# PFC-120W.net
KiCad netlist of a schematic drawn in Altium Designer
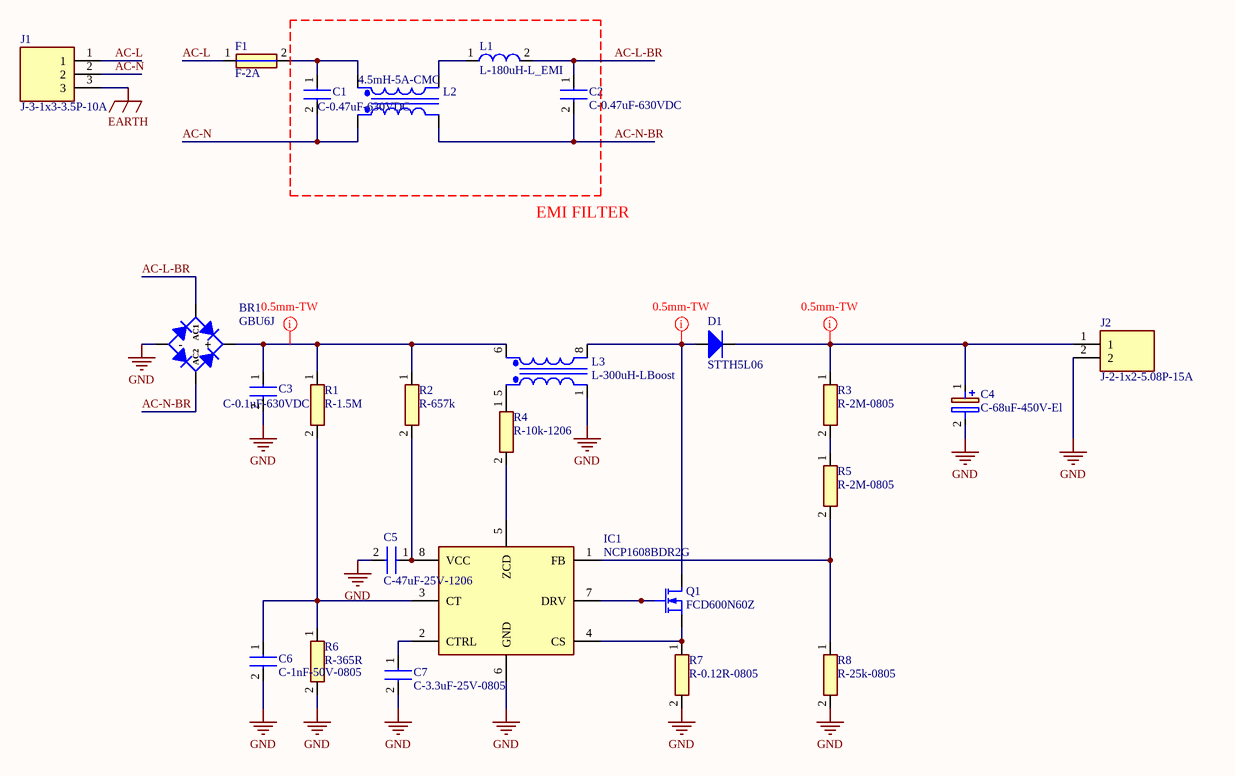
[diagram p0: PFC-120W.SchDoc]

(export (version "E")
  (design (tool "Eeschema 10.0.6"))
  (components
    (comp (ref "BR1")
      (value "GBU6J")
      (footprint "PFC-120W-Pcb-Lib:GBU6J")
      (description "Bridge Rectifier")
      (fields (field (name "MOUSER PART NUMBER") "905-GBU6J"))
      (libsource (lib "PFC-120W-Sch-Lib") (part "GBU6J"))
    )
    (comp (ref "C1")
      (value "C-0.47uF-630VDC")
      (footprint "PFC-120W-Pcb-Lib:ECWFA2J474JC")
      (description "Capacitor")
      (fields (field (name "MANUFACTURER_PART_NUMBER") "ECW-FA2J474JC"))
      (libsource (lib "PFC-120W-Sch-Lib") (part "C-0.47uF-630VDC"))
    )
    (comp (ref "C2")
      (value "C-0.47uF-630VDC")
      (footprint "PFC-120W-Pcb-Lib:ECWFA2J474JC")
      (description "Capacitor")
      (fields (field (name "MANUFACTURER_PART_NUMBER") "ECW-FA2J474JC"))
      (libsource (lib "PFC-120W-Sch-Lib") (part "C-0.47uF-630VDC"))
    )
    (comp (ref "C3")
      (value "C-0.1uF-630VDC")
      (footprint "PFC-120W-Pcb-Lib:BFC233923104")
      (description "Capacitor")
      (fields
        (field (name "MANUFACTURER_PART_NUMBER") "BFC233923104")
        (field (name "MOUSER PART NUMBER") "594-2222-339-23104")
      )
      (libsource (lib "PFC-120W-Sch-Lib") (part "C-0.1uF-630VDC"))
    )
    (comp (ref "C4")
      (value "C-68uF-450V-El")
      (footprint "PFC-120W-Pcb-Lib:CAPPRD750W80D1825H3750")
      (description "Capacitor Polarised")
      (fields (field (name "MANUFACTURER_PART_NUMBER") "UVY2W680MHD"))
      (libsource (lib "PFC-120W-Sch-Lib") (part "C-68uF-450V-El"))
    )
    (comp (ref "C5")
      (value "C-47uF-25V-1206")
      (footprint "PFC-120W-Pcb-Lib:CAPC3216X180N")
      (description "Capacitor")
      (fields
        (field (name "MANUFACTURER_PART_NUMBER") "C3216X5R1E476M160AC")
        (field (name "MOUSER PART NUMBER") "810-C3216X5R1E476M")
      )
      (libsource (lib "PFC-120W-Sch-Lib") (part "C-47uF-25V-1206"))
    )
    (comp (ref "C6")
      (value "C-1nF-50V-0805")
      (footprint "PFC-120W-Pcb-Lib:CAPC2012X135N")
      (description "Capacitor")
      (fields
        (field (name "MANUFACTURER_PART_NUMBER") "885382207004")
        (field (name "MOUSER PART NUMBER") "710-885382207004")
      )
      (libsource (lib "PFC-120W-Sch-Lib") (part "C-1nF-50V-0805"))
    )
    (comp (ref "C7")
      (value "C-3.3uF-25V-0805")
      (footprint "PFC-120W-Pcb-Lib:CAPC2012X145N")
      (description "Capacitor")
      (fields
        (field (name "MANUFACTURER_PART_NUMBER") "C2012X7R1E335M125AB")
        (field (name "MOUSER PART NUMBER") "810-C2012X7R1E335M")
      )
      (libsource (lib "PFC-120W-Sch-Lib") (part "C-3.3uF-25V-0805"))
    )
    (comp (ref "D1")
      (value "STTH5L06")
      (footprint "DPAK-STTH5L06")
      (description "Diode")
      (fields
        (field (name "MANUFACTURER") "STMicroelectronics")
        (field (name "MANUFACTURER PART NUMBER") "STTH5L06FP")
      )
      (libsource (lib "PFC-120W-Sch-Lib") (part "STTH5L06"))
    )
    (comp (ref "F1")
      (value "F-2A")
      (footprint "PFC-120W-Pcb-Lib:FUSC10131X312N")
      (description "Fuse")
      (fields
        (field (name "MANUFACTURER_PART_NUMBER") "0461002.ERT")
        (field (name "MOUSER PART NUMBER") "576-0461002.ERT")
      )
      (libsource (lib "PFC-120W-Sch-Lib") (part "F-2A"))
    )
    (comp (ref "IC1")
      (value "NCP1608BDR2G")
      (footprint "PFC-120W-Pcb-Lib:SOIC127P600X175-8N")
      (description "Integrated Circuit")
      (fields (field (name "MOUSER PART NUMBER") "863-NCP1608BDR2G"))
      (libsource (lib "PFC-120W-Sch-Lib") (part "NCP1608BDR2G"))
    )
    (comp (ref "J1")
      (value "J-3-1x3-3.5P-10A")
      (footprint "PFC-120W-Pcb-Lib:691214110003")
      (description "Connector")
      (fields
        (field (name "MANUFACTURER_PART_NUMBER") "691214110003")
        (field (name "MOUSER PART NUMBER") "710-691214110003")
      )
      (libsource (lib "PFC-120W-Sch-Lib") (part "J-3-1x3-3.5P-10A"))
    )
    (comp (ref "J2")
      (value "J-2-1x2-5.08P-15A")
      (footprint "PFC-120W-Pcb-Lib:RHDR2W90P0X508_1X2_1066X810X1000P")
      (description "Connector")
      (fields (field (name "MANUFACTURER_PART_NUMBER") "EDZ250/2"))
      (libsource (lib "PFC-120W-Sch-Lib") (part "J-2-1x2-5.08P-15A"))
    )
    (comp (ref "L1")
      (value "L-180uH-L_EMI")
      (footprint "PFC-120W-Pcb-Lib:AIRD03181K")
      (description "Inductor")
      (fields
        (field (name "MANUFACTURER_PART_NUMBER") "AIRD-03-181K")
        (field (name "MOUSER PART NUMBER") "815-AIRD-03-181K")
      )
      (libsource (lib "PFC-120W-Sch-Lib") (part "L-180uH-L_EMI"))
    )
    (comp (ref "L2")
      (value "4.5mH-5A-CMC")
      (footprint "PFC-120W-Pcb-Lib:SC05E45JH")
      (description "Filter")
      (fields
        (field (name "MANUFACTURER_PART_NUMBER") "SC-05-E45JH")
        (field (name "MOUSER PART NUMBER") "80-SC-05-E45JH")
      )
      (libsource (lib "PFC-120W-Sch-Lib") (part "4.5mH-5A-CMC"))
    )
    (comp (ref "L3")
      (value "L-300uH-LBoost")
      (footprint "L-300uH-LBoost")
      (description "Inductor")
      (fields
        (field (name "MANUFACTURER PART NUMBER") "PFC3125ER-301K05B-00")
        (field (name "MANUFACTURER") "TDK Corporation")
      )
      (libsource (lib "PFC-120W-Sch-Lib") (part "L-300uH-LBoost"))
    )
    (comp (ref "Q1")
      (value "FCD600N60Z")
      (footprint "PFC-120W-Pcb-Lib:DPAK-FCD600N60Z")
      (description "N-Mosfet")
      (fields (field (name "MANUFACTURER") "ON Semiconductor"))
      (libsource (lib "PFC-120W-Sch-Lib") (part "FCD600N60Z"))
    )
    (comp (ref "R1")
      (value "R-1.5M")
      (footprint "PFC-120W-Pcb-Lib:RESC3216X60N")
      (description "Resistor")
      (fields
        (field (name "MANUFACTURER_PART_NUMBER") "CRCW12061M50FKEA")
        (field (name "MOUSER PART NUMBER") "71-CRCW1206-1.5M-E3")
      )
      (libsource (lib "PFC-120W-Sch-Lib") (part "R-1.5M"))
    )
    (comp (ref "R2")
      (value "R-657k")
      (footprint "PFC-120W-Pcb-Lib:0805_RES")
      (description "Resistor")
      (fields
        (field (name "MANUFACTURER PART NUMBER") "RN73R2ATTD6573D25")
        (field (name "MANUFACTURER") "KOA Speer Electronics, Inc.")
      )
      (libsource (lib "PFC-120W-Sch-Lib") (part "R-657k"))
    )
    (comp (ref "R3")
      (value "R-2M-0805")
      (footprint "PFC-120W-Pcb-Lib:RESC2012X65N")
      (description "Resistor")
      (fields
        (field (name "MANUFACTURER_PART_NUMBER") "CPF0805B2M0E")
        (field (name "MOUSER PART NUMBER") "279-CPF0805B2M0E")
      )
      (libsource (lib "PFC-120W-Sch-Lib") (part "R-2M-0805"))
    )
    (comp (ref "R4")
      (value "R-10k-1206")
      (footprint "PFC-120W-Pcb-Lib:RESC3216X60N")
      (description "Resistor")
      (fields
        (field (name "MANUFACTURER_PART_NUMBER") "CRCW120610K0FKEB")
        (field (name "MOUSER PART NUMBER") "71-CRCW120610K0FKEB")
      )
      (libsource (lib "PFC-120W-Sch-Lib") (part "R-10k-1206"))
    )
    (comp (ref "R5")
      (value "R-2M-0805")
      (footprint "PFC-120W-Pcb-Lib:RESC2012X65N")
      (description "Resistor")
      (fields
        (field (name "MANUFACTURER_PART_NUMBER") "CPF0805B2M0E")
        (field (name "MOUSER PART NUMBER") "279-CPF0805B2M0E")
      )
      (libsource (lib "PFC-120W-Sch-Lib") (part "R-2M-0805"))
    )
    (comp (ref "R6")
      (value "R-365R")
      (footprint "PFC-120W-Pcb-Lib:RESC2012X65N")
      (description "Resistor")
      (fields
        (field (name "MANUFACTURER_PART_NUMBER") "CPF0805B365RE1")
        (field (name "MOUSER PART NUMBER") "279-CPF0805B365RE1")
      )
      (libsource (lib "PFC-120W-Sch-Lib") (part "R-365R-0805"))
    )
    (comp (ref "R7")
      (value "R-0.12R-0805")
      (footprint "PFC-120W-Pcb-Lib:RESC2012X60N")
      (description "Resistor")
      (fields
        (field (name "MANUFACTURER_PART_NUMBER") "RL0805FR-070R12L")
        (field (name "MOUSER PART NUMBER") "603-RL0805FR-070R12L")
      )
      (libsource (lib "PFC-120W-Sch-Lib") (part "R-0.12R-0805"))
    )
    (comp (ref "R8")
      (value "R-25k-0805")
      (footprint "PFC-120W-Pcb-Lib:RESC2012X65N")
      (description "Resistor")
      (fields
        (field (name "MANUFACTURER_PART_NUMBER") "CPF-A-0805B25KE1")
        (field (name "MOUSER PART NUMBER") "279-CPF-A-0805B25KE1")
      )
      (libsource (lib "PFC-120W-Sch-Lib") (part "R-25k-0805"))
    )
  )
  (nets
    (net (code "1") (name "/AC-L") (class "Default")
      (node (ref "F1") (pin "1") (pinfunction "1_1") (pintype "passive"))
      (node (ref "J1") (pin "1") (pinfunction "1_1") (pintype "passive"))
    )
    (net (code "2") (name "/AC-L-BR") (class "Default")
      (node (ref "BR1") (pin "2") (pinfunction "AC1_2") (pintype "passive"))
      (node (ref "C2") (pin "1") (pinfunction "1_1") (pintype "passive"))
      (node (ref "L1") (pin "2") (pinfunction "2_2") (pintype "passive"))
    )
    (net (code "3") (name "/AC-N") (class "Default")
      (node (ref "C1") (pin "2") (pinfunction "2_2") (pintype "passive"))
      (node (ref "J1") (pin "2") (pinfunction "2_2") (pintype "passive"))
      (node (ref "L2") (pin "3") (pinfunction "3_3") (pintype "passive"))
    )
    (net (code "4") (name "/AC-N-BR") (class "Default")
      (node (ref "BR1") (pin "3") (pinfunction "AC2_3") (pintype "passive"))
      (node (ref "C2") (pin "2") (pinfunction "2_2") (pintype "passive"))
      (node (ref "L2") (pin "4") (pinfunction "4_4") (pintype "passive"))
    )
    (net (code "5") (name "EARTH") (class "Default")
      (node (ref "J1") (pin "3") (pinfunction "3_3") (pintype "passive"))
    )
    (net (code "6") (name "GND") (class "Default")
      (node (ref "BR1") (pin "4") (pinfunction "-_4") (pintype "passive"))
      (node (ref "C3") (pin "2") (pinfunction "2_2") (pintype "passive"))
      (node (ref "C4") (pin "2") (pinfunction "-_2") (pintype "passive"))
      (node (ref "C5") (pin "2") (pinfunction "2_2") (pintype "passive"))
      (node (ref "C6") (pin "2") (pinfunction "2_2") (pintype "passive"))
      (node (ref "C7") (pin "2") (pinfunction "2_2") (pintype "passive"))
      (node (ref "IC1") (pin "6") (pinfunction "GND_6") (pintype "power_in"))
      (node (ref "J2") (pin "2") (pinfunction "2_2") (pintype "passive"))
      (node (ref "L3") (pin "1") (pinfunction "1_1") (pintype "passive"))
      (node (ref "R6") (pin "2") (pinfunction "2_2") (pintype "passive"))
      (node (ref "R7") (pin "2") (pinfunction "2_2") (pintype "passive"))
      (node (ref "R8") (pin "2") (pinfunction "2_2") (pintype "passive"))
    )
    (net (code "7") (name "Net-(BR1-+)") (class "Default")
      (node (ref "BR1") (pin "1") (pinfunction "+_1") (pintype "passive"))
      (node (ref "C3") (pin "1") (pinfunction "1_1") (pintype "passive"))
      (node (ref "L3") (pin "6") (pinfunction "6_6") (pintype "passive"))
      (node (ref "R1") (pin "1") (pinfunction "1_1") (pintype "passive"))
      (node (ref "R2") (pin "1") (pinfunction "1_1") (pintype "passive"))
    )
    (net (code "8") (name "Net-(C1-Pad1)") (class "Default")
      (node (ref "C1") (pin "1") (pinfunction "1_1") (pintype "passive"))
      (node (ref "F1") (pin "2") (pinfunction "2_2") (pintype "passive"))
      (node (ref "L2") (pin "1") (pinfunction "1_1") (pintype "passive"))
    )
    (net (code "9") (name "Net-(C4-+)") (class "Default")
      (node (ref "C4") (pin "1") (pinfunction "+_1") (pintype "passive"))
      (node (ref "D1") (pin "K") (pinfunction "K_K") (pintype "passive"))
      (node (ref "J2") (pin "1") (pinfunction "1_1") (pintype "passive"))
      (node (ref "R3") (pin "1") (pinfunction "1_1") (pintype "passive"))
    )
    (net (code "10") (name "Net-(D1-PadA)") (class "Default")
      (node (ref "D1") (pin "A") (pinfunction "A_A") (pintype "passive"))
      (node (ref "L3") (pin "8") (pinfunction "8_8") (pintype "passive"))
      (node (ref "Q1") (pin "D") (pinfunction "D_D") (pintype "passive"))
    )
    (net (code "11") (name "Net-(IC1-CS)") (class "Default")
      (node (ref "IC1") (pin "4") (pinfunction "CS_4") (pintype "passive"))
      (node (ref "Q1") (pin "S") (pinfunction "S_S") (pintype "passive"))
      (node (ref "R7") (pin "1") (pinfunction "1_1") (pintype "passive"))
    )
    (net (code "12") (name "Net-(IC1-CT)") (class "Default")
      (node (ref "C6") (pin "1") (pinfunction "1_1") (pintype "passive"))
      (node (ref "IC1") (pin "3") (pinfunction "CT_3") (pintype "passive"))
      (node (ref "R1") (pin "2") (pinfunction "2_2") (pintype "passive"))
      (node (ref "R6") (pin "1") (pinfunction "1_1") (pintype "passive"))
    )
    (net (code "13") (name "Net-(IC1-CTRL)") (class "Default")
      (node (ref "C7") (pin "1") (pinfunction "1_1") (pintype "passive"))
      (node (ref "IC1") (pin "2") (pinfunction "CTRL_2") (pintype "passive"))
    )
    (net (code "14") (name "Net-(IC1-DRV)") (class "Default")
      (node (ref "IC1") (pin "7") (pinfunction "DRV_7") (pintype "passive"))
      (node (ref "Q1") (pin "G") (pinfunction "G_G") (pintype "passive"))
    )
    (net (code "15") (name "Net-(IC1-FB)") (class "Default")
      (node (ref "IC1") (pin "1") (pinfunction "FB_1") (pintype "passive"))
      (node (ref "R5") (pin "2") (pinfunction "2_2") (pintype "passive"))
      (node (ref "R8") (pin "1") (pinfunction "1_1") (pintype "passive"))
    )
    (net (code "16") (name "Net-(IC1-VCC)") (class "Default")
      (node (ref "C5") (pin "1") (pinfunction "1_1") (pintype "passive"))
      (node (ref "IC1") (pin "8") (pinfunction "VCC_8") (pintype "power_in"))
      (node (ref "R2") (pin "2") (pinfunction "2_2") (pintype "passive"))
    )
    (net (code "17") (name "Net-(IC1-ZCD)") (class "Default")
      (node (ref "IC1") (pin "5") (pinfunction "ZCD_5") (pintype "passive"))
      (node (ref "R4") (pin "2") (pinfunction "2_2") (pintype "passive"))
    )
    (net (code "18") (name "Net-(L1-Pad1)") (class "Default")
      (node (ref "L1") (pin "1") (pinfunction "1_1") (pintype "passive"))
      (node (ref "L2") (pin "2") (pinfunction "2_2") (pintype "passive"))
    )
    (net (code "19") (name "Net-(L3-Pad5)") (class "Default")
      (node (ref "L3") (pin "5") (pinfunction "5_5") (pintype "passive"))
      (node (ref "R4") (pin "1") (pinfunction "1_1") (pintype "passive"))
    )
    (net (code "20") (name "Net-(R3-Pad2)") (class "Default")
      (node (ref "R3") (pin "2") (pinfunction "2_2") (pintype "passive"))
      (node (ref "R5") (pin "1") (pinfunction "1_1") (pintype "passive"))
    )
  )
)
